# deneme1.net
KiCad netlist of a schematic drawn in EAGLE
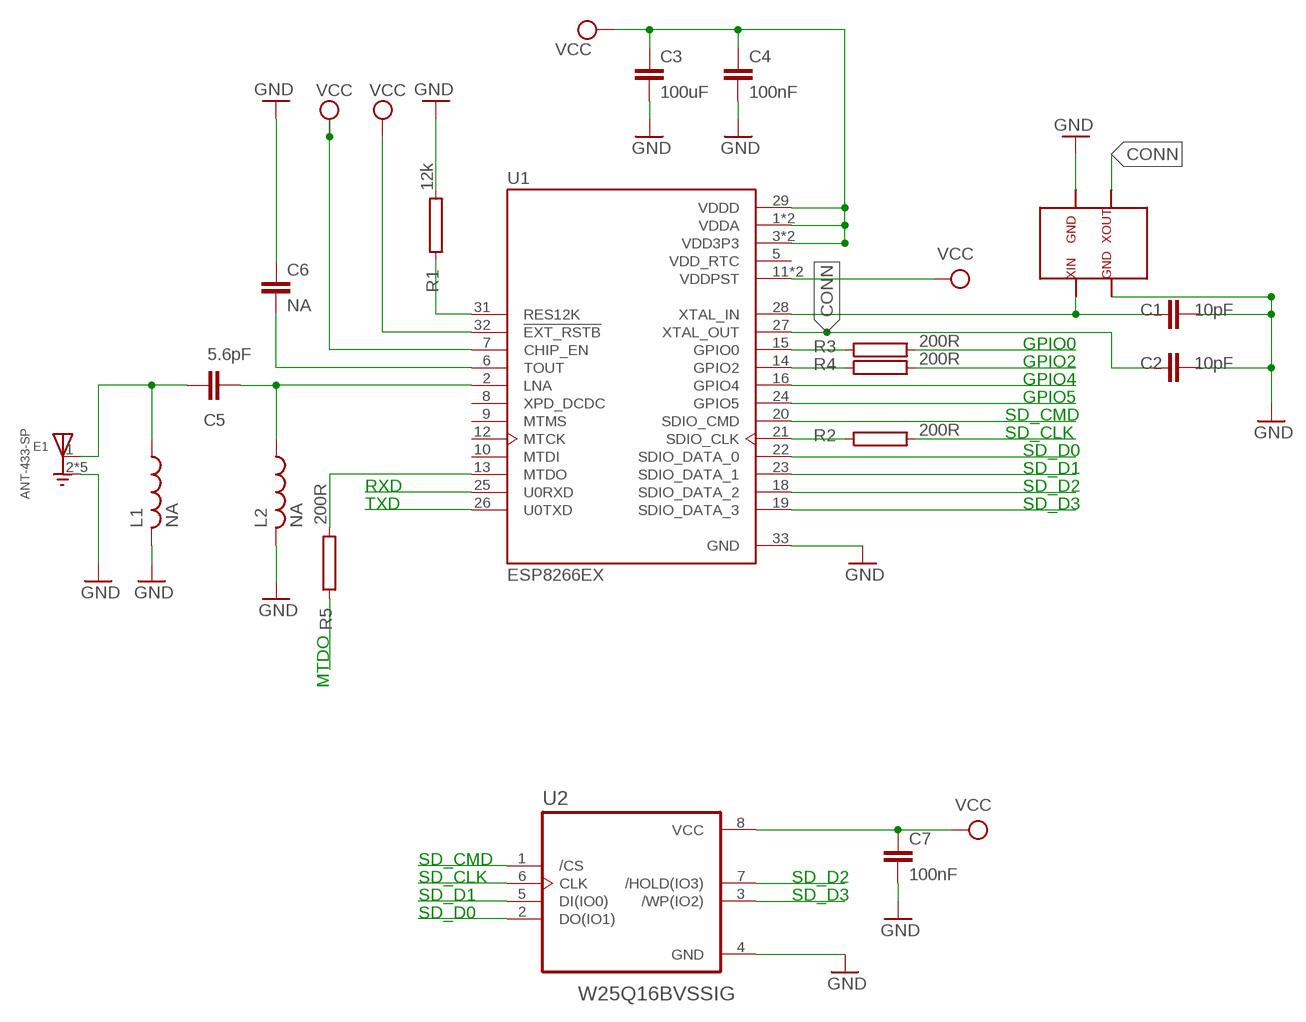
[diagram p0: schematic, sheet 1]

(export (version "E")
  (design (tool "Eeschema 10.0.6"))
  (components
    (comp (ref "C1")
      (value "10pF")
      (footprint "eagle-import:C5B2.5")
      (libsource (lib "eagle-import") (part "C5/2.5"))
    )
    (comp (ref "C2")
      (value "10pF")
      (footprint "eagle-import:C5B2.5")
      (libsource (lib "eagle-import") (part "C5/2.5"))
    )
    (comp (ref "C3")
      (value "100uF")
      (footprint "eagle-import:C5B2.5")
      (libsource (lib "eagle-import") (part "C5/2.5"))
    )
    (comp (ref "C4")
      (value "100nF")
      (footprint "eagle-import:C5B2.5")
      (libsource (lib "eagle-import") (part "C5/2.5"))
    )
    (comp (ref "C5")
      (value "5.6pF")
      (footprint "eagle-import:C5B2.5")
      (libsource (lib "eagle-import") (part "C5/2.5"))
    )
    (comp (ref "C6")
      (value "NA")
      (footprint "eagle-import:C5B2.5")
      (libsource (lib "eagle-import") (part "C5/2.5"))
    )
    (comp (ref "C7")
      (value "100nF")
      (footprint "eagle-import:C5B2.5")
      (libsource (lib "eagle-import") (part "C5/2.5"))
    )
    (comp (ref "E1")
      (value "ANT-433-SP")
      (footprint "eagle-import:XDCR_ANT-433-SP")
      (fields (field (name "MF") "Linx Technologies"))
      (libsource (lib "eagle-import") (part "ANT-433-SP"))
    )
    (comp (ref "L1")
      (value "NA")
      (footprint "eagle-import:0204_5")
      (libsource (lib "eagle-import") (part "L-US0204/5"))
    )
    (comp (ref "L2")
      (value "NA")
      (footprint "eagle-import:0204_5")
      (libsource (lib "eagle-import") (part "L-US0204/5"))
    )
    (comp (ref "R1")
      (value "12k")
      (footprint "eagle-import:TO-247-2V")
      (libsource (lib "eagle-import") (part "RMG100-V"))
    )
    (comp (ref "R2")
      (value "200R")
      (footprint "eagle-import:TO-247-2V")
      (libsource (lib "eagle-import") (part "RMG100-V"))
    )
    (comp (ref "R3")
      (value "200R")
      (footprint "eagle-import:TO-247-2V")
      (libsource (lib "eagle-import") (part "RMG100-V"))
    )
    (comp (ref "R4")
      (value "200R")
      (footprint "eagle-import:TO-247-2V")
      (libsource (lib "eagle-import") (part "RMG100-V"))
    )
    (comp (ref "R5")
      (value "200R")
      (footprint "eagle-import:TO-247-2V")
      (libsource (lib "eagle-import") (part "RMG100-V"))
    )
    (comp (ref "U1")
      (value "ESP8266EX")
      (footprint "eagle-import:QFN50P500X500X80-33N")
      (fields (field (name "MF") "Espressif Systems"))
      (libsource (lib "eagle-import") (part "ESP8266EX"))
    )
    (comp (ref "U2")
      (value "W25Q16BVSSIG")
      (footprint "eagle-import:SOIC127P790X216-8N")
      (fields (field (name "MF") "Winbond"))
      (libsource (lib "eagle-import") (part "W25Q16BVSSIG"))
    )
  )
  (nets
    (net (code "1") (name "/VDD_RTC") (class "Default")
      (node (ref "U1") (pin "5") (pinfunction "VDD_RTC_5") (pintype "power_in"))
    )
    (net (code "2") (name "CONN") (class "Default")
      (node (ref "C2") (pin "1") (pinfunction "1_1") (pintype "passive"))
      (node (ref "U1") (pin "27") (pinfunction "XTAL_OUT_27") (pintype "bidirectional"))
    )
    (net (code "3") (name "GND") (class "Default")
      (node (ref "C1") (pin "2") (pinfunction "2_2") (pintype "passive"))
      (node (ref "C2") (pin "2") (pinfunction "2_2") (pintype "passive"))
      (node (ref "C3") (pin "2") (pinfunction "2_2") (pintype "passive"))
      (node (ref "C4") (pin "2") (pinfunction "2_2") (pintype "passive"))
      (node (ref "C6") (pin "1") (pinfunction "1_1") (pintype "passive"))
      (node (ref "C7") (pin "2") (pinfunction "2_2") (pintype "passive"))
      (node (ref "E1") (pin "2") (pinfunction "GND_2") (pintype "power_in"))
      (node (ref "E1") (pin "3") (pinfunction "GND_3") (pintype "power_in"))
      (node (ref "E1") (pin "4") (pinfunction "GND_4") (pintype "power_in"))
      (node (ref "E1") (pin "5") (pinfunction "GND_5") (pintype "power_in"))
      (node (ref "E1") (pin "6") (pinfunction "GND_6") (pintype "power_in"))
      (node (ref "L1") (pin "2") (pinfunction "2_2") (pintype "passive"))
      (node (ref "L2") (pin "2") (pinfunction "2_2") (pintype "passive"))
      (node (ref "R1") (pin "2") (pinfunction "2_2") (pintype "passive"))
      (node (ref "U1") (pin "33") (pinfunction "GND_33") (pintype "power_in"))
      (node (ref "U2") (pin "4") (pinfunction "GND_4") (pintype "power_in"))
    )
    (net (code "4") (name "Net-(E1-FEEDING)") (class "Default")
      (node (ref "C5") (pin "2") (pinfunction "2_2") (pintype "passive"))
      (node (ref "E1") (pin "1") (pinfunction "FEEDING_1") (pintype "passive"))
      (node (ref "L1") (pin "1") (pinfunction "1_1") (pintype "passive"))
    )
    (net (code "5") (name "Net-(U1-GPIO0)") (class "Default")
      (node (ref "R3") (pin "1") (pinfunction "1_1") (pintype "passive"))
      (node (ref "U1") (pin "15") (pinfunction "GPIO0_15") (pintype "bidirectional"))
    )
    (net (code "6") (name "Net-(U1-GPIO2)") (class "Default")
      (node (ref "R4") (pin "1") (pinfunction "1_1") (pintype "passive"))
      (node (ref "U1") (pin "14") (pinfunction "GPIO2_14") (pintype "bidirectional"))
    )
    (net (code "7") (name "Net-(U1-LNA)") (class "Default")
      (node (ref "C5") (pin "1") (pinfunction "1_1") (pintype "passive"))
      (node (ref "L2") (pin "1") (pinfunction "1_1") (pintype "passive"))
      (node (ref "U1") (pin "2") (pinfunction "LNA_2") (pintype "bidirectional"))
    )
    (net (code "8") (name "Net-(U1-MTDO)") (class "Default")
      (node (ref "R5") (pin "2") (pinfunction "2_2") (pintype "passive"))
      (node (ref "U1") (pin "13") (pinfunction "MTDO_13") (pintype "bidirectional"))
    )
    (net (code "9") (name "Net-(U1-RES12K)") (class "Default")
      (node (ref "R1") (pin "1") (pinfunction "1_1") (pintype "passive"))
      (node (ref "U1") (pin "31") (pinfunction "RES12K_31") (pintype "input"))
    )
    (net (code "10") (name "Net-(U1-SDIO_CLK)") (class "Default")
      (node (ref "R2") (pin "1") (pinfunction "1_1") (pintype "passive"))
      (node (ref "U1") (pin "21") (pinfunction "SDIO_CLK_21") (pintype "bidirectional"))
    )
    (net (code "11") (name "Net-(U1-TOUT)") (class "Default")
      (node (ref "C6") (pin "2") (pinfunction "2_2") (pintype "passive"))
      (node (ref "U1") (pin "6") (pinfunction "TOUT_6") (pintype "input"))
    )
    (net (code "12") (name "Net-(U1-XTAL_IN)") (class "Default")
      (node (ref "C1") (pin "1") (pinfunction "1_1") (pintype "passive"))
      (node (ref "U1") (pin "28") (pinfunction "XTAL_IN_28") (pintype "bidirectional"))
    )
    (net (code "13") (name "VCC") (class "Default")
      (node (ref "C3") (pin "1") (pinfunction "1_1") (pintype "passive"))
      (node (ref "C4") (pin "1") (pinfunction "1_1") (pintype "passive"))
      (node (ref "C7") (pin "1") (pinfunction "1_1") (pintype "passive"))
      (node (ref "U1") (pin "1") (pinfunction "VDDA_1") (pintype "power_in"))
      (node (ref "U1") (pin "11") (pinfunction "VDDPST_11") (pintype "power_in"))
      (node (ref "U1") (pin "17") (pinfunction "VDDPST_17") (pintype "power_in"))
      (node (ref "U1") (pin "29") (pinfunction "VDDD_29") (pintype "power_in"))
      (node (ref "U1") (pin "3") (pinfunction "VDD3P3_3") (pintype "power_in"))
      (node (ref "U1") (pin "30") (pinfunction "VDDA_30") (pintype "power_in"))
      (node (ref "U1") (pin "32") (pinfunction "~{EXT_RSTB}_32") (pintype "input"))
      (node (ref "U1") (pin "4") (pinfunction "VDD3P3_4") (pintype "power_in"))
      (node (ref "U1") (pin "7") (pinfunction "CHIP_EN_7") (pintype "input"))
      (node (ref "U2") (pin "8") (pinfunction "VCC_8") (pintype "power_in"))
    )
    (net (code "14") (name "unconnected-(R2-Pad2)") (class "Default")
      (node (ref "R2") (pin "2") (pinfunction "2_2") (pintype "passive"))
    )
    (net (code "15") (name "unconnected-(R3-Pad2)") (class "Default")
      (node (ref "R3") (pin "2") (pinfunction "2_2") (pintype "passive"))
    )
    (net (code "16") (name "unconnected-(R4-Pad2)") (class "Default")
      (node (ref "R4") (pin "2") (pinfunction "2_2") (pintype "passive"))
    )
    (net (code "17") (name "unconnected-(R5-Pad1)") (class "Default")
      (node (ref "R5") (pin "1") (pinfunction "1_1") (pintype "passive"))
    )
    (net (code "18") (name "unconnected-(U1-GPIO4-Pad16)") (class "Default")
      (node (ref "U1") (pin "16") (pinfunction "GPIO4_16") (pintype "bidirectional"))
    )
    (net (code "19") (name "unconnected-(U1-GPIO5-Pad24)") (class "Default")
      (node (ref "U1") (pin "24") (pinfunction "GPIO5_24") (pintype "bidirectional"))
    )
    (net (code "20") (name "unconnected-(U1-MTCK-Pad12)") (class "Default")
      (node (ref "U1") (pin "12") (pinfunction "MTCK_12") (pintype "bidirectional"))
    )
    (net (code "21") (name "unconnected-(U1-MTDI-Pad10)") (class "Default")
      (node (ref "U1") (pin "10") (pinfunction "MTDI_10") (pintype "bidirectional"))
    )
    (net (code "22") (name "unconnected-(U1-MTMS-Pad9)") (class "Default")
      (node (ref "U1") (pin "9") (pinfunction "MTMS_9") (pintype "bidirectional"))
    )
    (net (code "23") (name "unconnected-(U1-SDIO_CMD-Pad20)") (class "Default")
      (node (ref "U1") (pin "20") (pinfunction "SDIO_CMD_20") (pintype "bidirectional"))
    )
    (net (code "24") (name "unconnected-(U1-SDIO_DATA_0-Pad22)") (class "Default")
      (node (ref "U1") (pin "22") (pinfunction "SDIO_DATA_0_22") (pintype "bidirectional"))
    )
    (net (code "25") (name "unconnected-(U1-SDIO_DATA_1-Pad23)") (class "Default")
      (node (ref "U1") (pin "23") (pinfunction "SDIO_DATA_1_23") (pintype "bidirectional"))
    )
    (net (code "26") (name "unconnected-(U1-SDIO_DATA_2-Pad18)") (class "Default")
      (node (ref "U1") (pin "18") (pinfunction "SDIO_DATA_2_18") (pintype "bidirectional"))
    )
    (net (code "27") (name "unconnected-(U1-SDIO_DATA_3-Pad19)") (class "Default")
      (node (ref "U1") (pin "19") (pinfunction "SDIO_DATA_3_19") (pintype "bidirectional"))
    )
    (net (code "28") (name "unconnected-(U1-U0RXD-Pad25)") (class "Default")
      (node (ref "U1") (pin "25") (pinfunction "U0RXD_25") (pintype "bidirectional"))
    )
    (net (code "29") (name "unconnected-(U1-U0TXD-Pad26)") (class "Default")
      (node (ref "U1") (pin "26") (pinfunction "U0TXD_26") (pintype "bidirectional"))
    )
    (net (code "30") (name "unconnected-(U1-XPD_DCDC-Pad8)") (class "Default")
      (node (ref "U1") (pin "8") (pinfunction "XPD_DCDC_8") (pintype "bidirectional"))
    )
    (net (code "31") (name "unconnected-(U2-CLK-Pad6)") (class "Default")
      (node (ref "U2") (pin "6") (pinfunction "CLK_6") (pintype "input"))
    )
    (net (code "32") (name "unconnected-(U2-DI(IO0)-Pad5)") (class "Default")
      (node (ref "U2") (pin "5") (pinfunction "DI(IO0)_5") (pintype "bidirectional"))
    )
    (net (code "33") (name "unconnected-(U2-DO(IO1)-Pad2)") (class "Default")
      (node (ref "U2") (pin "2") (pinfunction "DO(IO1)_2") (pintype "bidirectional"))
    )
    (net (code "34") (name "unconnected-(U2-{slash}CS-Pad1)") (class "Default")
      (node (ref "U2") (pin "1") (pinfunction "/CS_1") (pintype "input"))
    )
    (net (code "35") (name "unconnected-(U2-{slash}HOLD(IO3)-Pad7)") (class "Default")
      (node (ref "U2") (pin "7") (pinfunction "/HOLD(IO3)_7") (pintype "bidirectional"))
    )
    (net (code "36") (name "unconnected-(U2-{slash}WP(IO2)-Pad3)") (class "Default")
      (node (ref "U2") (pin "3") (pinfunction "/WP(IO2)_3") (pintype "bidirectional"))
    )
  )
)
